# Sheet1.net
KiCad netlist of a schematic drawn in Altium Designer
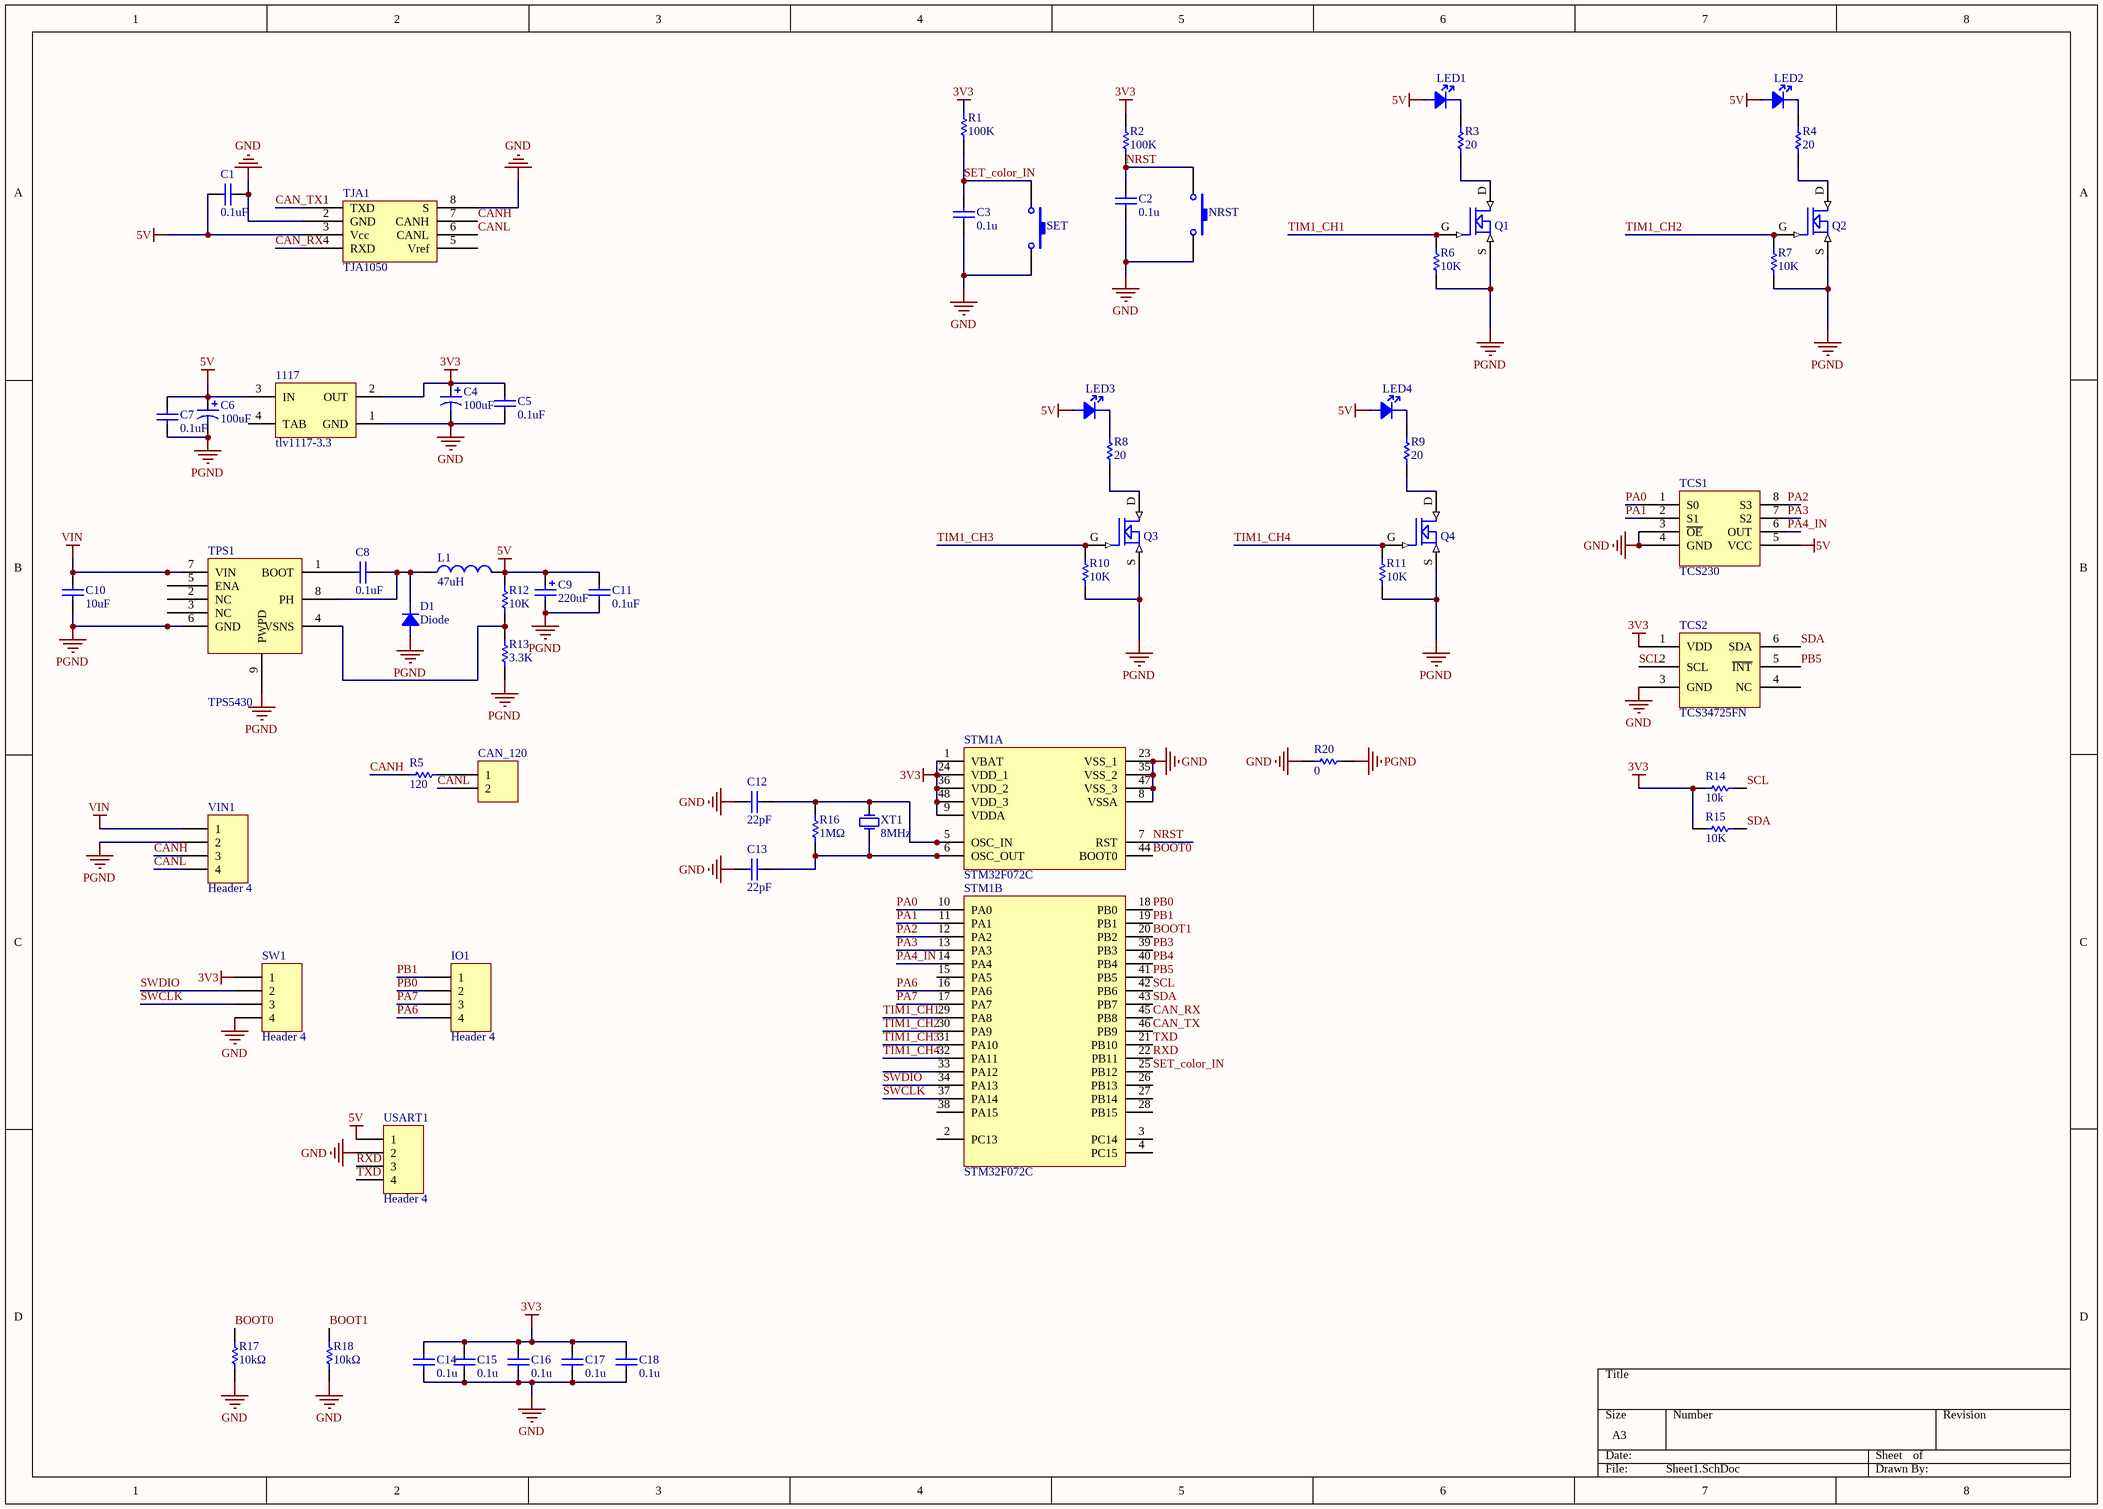
[diagram p0: Sheet1.SchDoc]

(export (version "E")
  (design (tool "Eeschema 10.0.6"))
  (components
    (comp (ref "1117")
      (value "tlv1117-3.3")
      (footprint "LM1117")
      (description "800mA Low-Dropout Linear Regulator")
      (fields
        (field (name "PARTNUMBER") "LM1117IMP-5.0")
        (field (name "MANUFACTURER") "National Semiconductor")
        (field (name "PUBLISHER") "Altium Limited")
      )
      (libsource (lib "K60-mainboard-v3.1") (part "LM1117IMP-5.0"))
    )
    (comp (ref "C1")
      (value "0.1uF")
      (footprint "CAP-MLCC-0603")
      (description "Capacitor")
      (fields (field (name "Comment") "Cap") (field (name "PUBLISHER") "Altium Limited"))
      (libsource (lib "K60-mainboard-v3.1") (part "Cap"))
    )
    (comp (ref "C2")
      (value "0.1u")
      (footprint "CAP-MLCC-0603")
      (description "无极性电容")
      (fields (field (name "PUBLISHER") "Altium Limited"))
      (libsource (lib "Libraries_2014_0618") (part "CAP"))
    )
    (comp (ref "C3")
      (value "0.1u")
      (footprint "CAP-MLCC-0603")
      (description "无极性电容")
      (fields (field (name "PUBLISHER") "Altium Limited"))
      (libsource (lib "Libraries_2014_0618") (part "CAP"))
    )
    (comp (ref "C4")
      (value "100uF")
      (footprint "6032C")
      (description "Polarized Capacitor (Surface Mount)")
      (fields (field (name "Comment") "Cap Pol3") (field (name "PUBLISHER") "Altium Limited"))
      (libsource (lib "K60-mainboard-v3.1") (part "Cap Pol3"))
    )
    (comp (ref "C5")
      (value "0.1uF")
      (footprint "CAP-MLCC-0603")
      (description "Capacitor")
      (fields (field (name "Comment") "Cap") (field (name "PUBLISHER") "Altium Limited"))
      (libsource (lib "K60-mainboard-v3.1") (part "Cap"))
    )
    (comp (ref "C6")
      (value "100uF")
      (footprint "6032C")
      (description "Polarized Capacitor (Surface Mount)")
      (fields (field (name "Comment") "Cap Pol3") (field (name "PUBLISHER") "Altium Limited"))
      (libsource (lib "K60-mainboard-v3.1") (part "Cap Pol3"))
    )
    (comp (ref "C7")
      (value "0.1uF")
      (footprint "CAP-MLCC-0603")
      (description "Capacitor")
      (fields (field (name "Comment") "Cap") (field (name "PUBLISHER") "Altium Limited"))
      (libsource (lib "K60-mainboard-v3.1") (part "Cap"))
    )
    (comp (ref "C8")
      (value "0.1uF")
      (footprint "CAP-MLCC-0603")
      (description "Capacitor")
      (fields (field (name "Comment") "Cap") (field (name "PUBLISHER") "Altium Limited"))
      (libsource (lib "K60-mainboard-v3.1") (part "Cap"))
    )
    (comp (ref "C9")
      (value "220uF")
      (footprint "6032C")
      (description "Polarized Capacitor (Radial)")
      (fields (field (name "Comment") "Cap Pol1") (field (name "PUBLISHER") "Altium Limited"))
      (libsource (lib "K60-mainboard-v3.1") (part "Cap Pol1"))
    )
    (comp (ref "C10")
      (value "10uF")
      (footprint "0805C")
      (description "Capacitor")
      (fields (field (name "Comment") "Cap") (field (name "PUBLISHER") "Altium Limited"))
      (libsource (lib "K60-mainboard-v3.1") (part "Cap"))
    )
    (comp (ref "C11")
      (value "0.1uF")
      (footprint "CAP-MLCC-0603")
      (description "Capacitor")
      (fields (field (name "Comment") "Cap") (field (name "PUBLISHER") "Altium Limited"))
      (libsource (lib "K60-mainboard-v3.1") (part "Cap"))
    )
    (comp (ref "C12")
      (value "22pF")
      (footprint "CAP-MLCC-0603")
      (description "无极性电容")
      (fields (field (name "PUBLISHER") "Altium Limited"))
      (libsource (lib "Libraries_2014_0618") (part "CAP"))
    )
    (comp (ref "C13")
      (value "22pF")
      (footprint "CAP-MLCC-0603")
      (description "无极性电容")
      (fields (field (name "PUBLISHER") "Altium Limited"))
      (libsource (lib "Libraries_2014_0618") (part "CAP"))
    )
    (comp (ref "C14")
      (value "0.1u")
      (footprint "CAP-MLCC-0603")
      (description "无极性电容")
      (fields (field (name "PUBLISHER") "Altium Limited"))
      (libsource (lib "Libraries_2014_0618") (part "CAP"))
    )
    (comp (ref "C15")
      (value "0.1u")
      (footprint "CAP-MLCC-0603")
      (description "无极性电容")
      (fields (field (name "PUBLISHER") "Altium Limited"))
      (libsource (lib "Libraries_2014_0618") (part "CAP"))
    )
    (comp (ref "C16")
      (value "0.1u")
      (footprint "CAP-MLCC-0603")
      (description "无极性电容")
      (fields (field (name "PUBLISHER") "Altium Limited"))
      (libsource (lib "Libraries_2014_0618") (part "CAP"))
    )
    (comp (ref "C17")
      (value "0.1u")
      (footprint "CAP-MLCC-0603")
      (description "无极性电容")
      (fields (field (name "PUBLISHER") "Altium Limited"))
      (libsource (lib "Libraries_2014_0618") (part "CAP"))
    )
    (comp (ref "C18")
      (value "0.1u")
      (footprint "CAP-MLCC-0603")
      (description "无极性电容")
      (fields (field (name "PUBLISHER") "Altium Limited"))
      (libsource (lib "Libraries_2014_0618") (part "CAP"))
    )
    (comp (ref "CAN_120")
      (value "Header 2")
      (footprint "SIP2")
      (description "Header, 2-Pin")
      (fields (field (name "PUBLISHER") "Altium Limited"))
      (libsource (lib "Libraries_2014_0618") (part "Header 2"))
    )
    (comp (ref "D1") (value "Diode") (footprint "SS34") (libsource (lib "K60-mainboard-v3.1") (part "Diode")))
    (comp (ref "IO1")
      (value "Header 4")
      (footprint "HDR1X4")
      (description "Header, 4-Pin")
      (fields (field (name "PUBLISHER") "Altium Limited"))
      (libsource (lib "K60-mainboard-v3.1") (part "Header 4"))
    )
    (comp (ref "L1")
      (value "47uH")
      (footprint "IND_CD52")
      (description "Inductor")
      (fields (field (name "PUBLISHER") "Altium Limited"))
      (libsource (lib "smartcar_example") (part "Inductor"))
    )
    (comp (ref "LED1")
      (value "lED")
      (footprint "LED直插8MM")
      (description "LED")
      (libsource (lib "K60-mainboard-v3.1") (part "00-D-LED"))
    )
    (comp (ref "LED2")
      (value "lED")
      (footprint "LED直插8MM")
      (description "LED")
      (libsource (lib "K60-mainboard-v3.1") (part "00-D-LED"))
    )
    (comp (ref "LED3")
      (value "lED")
      (footprint "LED直插8MM")
      (description "LED")
      (libsource (lib "K60-mainboard-v3.1") (part "00-D-LED"))
    )
    (comp (ref "LED4")
      (value "lED")
      (footprint "LED直插8MM")
      (description "LED")
      (libsource (lib "K60-mainboard-v3.1") (part "00-D-LED"))
    )
    (comp (ref "NRST")
      (value "SW-PB")
      (footprint "KEY")
      (description "Switch")
      (fields (field (name "PUBLISHER") "Altium Limited"))
      (libsource (lib "附加元件") (part "SW-PB"))
    )
    (comp (ref "Q1")
      (value "MOSFET N")
      (footprint "NMOS_SOT23")
      (libsource (lib "K60-mainboard-v3.1") (part "MOSFET N"))
    )
    (comp (ref "Q2")
      (value "MOSFET N")
      (footprint "NMOS_SOT23")
      (libsource (lib "K60-mainboard-v3.1") (part "MOSFET N"))
    )
    (comp (ref "Q3")
      (value "MOSFET N")
      (footprint "NMOS_SOT23")
      (libsource (lib "K60-mainboard-v3.1") (part "MOSFET N"))
    )
    (comp (ref "Q4")
      (value "MOSFET N")
      (footprint "NMOS_SOT23")
      (libsource (lib "K60-mainboard-v3.1") (part "MOSFET N"))
    )
    (comp (ref "R1")
      (value "100K")
      (footprint "RES-0603")
      (description "电阻")
      (fields (field (name "Comment") "RES") (field (name "PUBLISHER") "Altium Limited"))
      (libsource (lib "Libraries_2014_0215") (part "RES"))
    )
    (comp (ref "R2")
      (value "100K")
      (footprint "RES-0603")
      (description "电阻")
      (fields (field (name "Comment") "RES") (field (name "PUBLISHER") "Altium Limited"))
      (libsource (lib "Libraries_2014_0215") (part "RES"))
    )
    (comp (ref "R3")
      (value "20")
      (footprint "RES-0805")
      (description "电阻")
      (fields (field (name "PUBLISHER") "Altium Limited"))
      (libsource (lib "Libraries_2014_0618") (part "RES"))
    )
    (comp (ref "R4")
      (value "20")
      (footprint "RES-0805")
      (description "电阻")
      (fields (field (name "PUBLISHER") "Altium Limited"))
      (libsource (lib "Libraries_2014_0618") (part "RES"))
    )
    (comp (ref "R5")
      (value "120")
      (footprint "RES-0603")
      (description "Resistor")
      (fields (field (name "Comment") "Res1") (field (name "PUBLISHER") "Altium Limited"))
      (libsource (lib "K60-mainboard-v3.1") (part "Res1"))
    )
    (comp (ref "R6")
      (value "10K")
      (footprint "RES-0603")
      (description "电阻")
      (fields (field (name "PUBLISHER") "Altium Limited"))
      (libsource (lib "Libraries_2014_0618") (part "RES"))
    )
    (comp (ref "R7")
      (value "10K")
      (footprint "RES-0603")
      (description "电阻")
      (fields (field (name "PUBLISHER") "Altium Limited"))
      (libsource (lib "Libraries_2014_0618") (part "RES"))
    )
    (comp (ref "R8")
      (value "20")
      (footprint "RES-0805")
      (description "电阻")
      (fields (field (name "PUBLISHER") "Altium Limited"))
      (libsource (lib "Libraries_2014_0618") (part "RES"))
    )
    (comp (ref "R9")
      (value "20")
      (footprint "RES-0805")
      (description "电阻")
      (fields (field (name "PUBLISHER") "Altium Limited"))
      (libsource (lib "Libraries_2014_0618") (part "RES"))
    )
    (comp (ref "R10")
      (value "10K")
      (footprint "RES-0603")
      (description "电阻")
      (fields (field (name "PUBLISHER") "Altium Limited"))
      (libsource (lib "Libraries_2014_0618") (part "RES"))
    )
    (comp (ref "R11")
      (value "10K")
      (footprint "RES-0603")
      (description "电阻")
      (fields (field (name "PUBLISHER") "Altium Limited"))
      (libsource (lib "Libraries_2014_0618") (part "RES"))
    )
    (comp (ref "R12")
      (value "10K")
      (footprint "RES-0603")
      (description "Resistor")
      (fields (field (name "Comment") "Res1") (field (name "PUBLISHER") "Altium Limited"))
      (libsource (lib "K60-mainboard-v3.1") (part "Res1"))
    )
    (comp (ref "R13")
      (value "3.3K")
      (footprint "RES-0603")
      (description "Resistor")
      (fields (field (name "Comment") "Res1") (field (name "PUBLISHER") "Altium Limited"))
      (libsource (lib "K60-mainboard-v3.1") (part "Res1"))
    )
    (comp (ref "R14")
      (value "10k")
      (footprint "RES-0603")
      (description "电阻")
      (fields (field (name "PUBLISHER") "Altium Limited"))
      (libsource (lib "Libraries_2014_0618") (part "RES"))
    )
    (comp (ref "R15")
      (value "10K")
      (footprint "RES-0603")
      (description "电阻")
      (fields (field (name "PUBLISHER") "Altium Limited"))
      (libsource (lib "Libraries_2014_0618") (part "RES"))
    )
    (comp (ref "R16")
      (value "1MΩ")
      (footprint "RES-0603")
      (description "电阻")
      (fields (field (name "PUBLISHER") "Altium Limited"))
      (libsource (lib "Libraries_2014_0618") (part "RES"))
    )
    (comp (ref "R17")
      (value "10kΩ")
      (footprint "RES-0603")
      (description "电阻")
      (fields (field (name "Comment") "RES") (field (name "PUBLISHER") "Altium Limited"))
      (libsource (lib "Libraries_2014_0215") (part "RES"))
    )
    (comp (ref "R18")
      (value "10kΩ")
      (footprint "RES-0603")
      (description "电阻")
      (fields (field (name "Comment") "RES") (field (name "PUBLISHER") "Altium Limited"))
      (libsource (lib "Libraries_2014_0215") (part "RES"))
    )
    (comp (ref "R20")
      (value "0")
      (footprint "RES-0805")
      (description "电阻")
      (fields (field (name "PUBLISHER") "Altium Limited"))
      (libsource (lib "Libraries_2014_0618") (part "RES"))
    )
    (comp (ref "SET")
      (value "SW-PB")
      (footprint "KEY")
      (description "Switch")
      (fields (field (name "PUBLISHER") "Altium Limited"))
      (libsource (lib "附加元件") (part "SW-PB"))
    )
    (comp (ref "STM1")
      (value "STM32F072C")
      (footprint "PCB_IntegratedCircuit:LQFP_P0.5_48")
      (description "MCU")
      (libsource (lib "SCH_IntegratedCircuit") (part "STM32F103C"))
    )
    (comp (ref "SW1")
      (value "Header 4")
      (footprint "HDR1X4")
      (description "Header, 4-Pin")
      (fields (field (name "PUBLISHER") "Altium Limited"))
      (libsource (lib "K60-mainboard-v3.1") (part "Header 4"))
    )
    (comp (ref "TCS1")
      (value "TCS230")
      (footprint "SOP_E150_8")
      (libsource (lib "SCH_IntegratedCircuit") (part "TCS230"))
    )
    (comp (ref "TCS2")
      (value "TCS34725FN")
      (footprint "DFN-6")
      (description "颜色传感器")
      (libsource (lib "SCH_IntegratedCircuit") (part "TCS34725FN"))
    )
    (comp (ref "TJA1")
      (value "TJA1050")
      (footprint "TJA1050")
      (description "CAN总线收发器")
      (libsource (lib "Libraries_2014_0618") (part "TJA1050"))
    )
    (comp (ref "TPS1")
      (value "TPS5430")
      (footprint "TPS5430")
      (libsource (lib "K60-mainboard-v3.1") (part "TPS5430"))
    )
    (comp (ref "USART1")
      (value "Header 4")
      (footprint "HDR1X4")
      (description "Header, 4-Pin")
      (fields (field (name "PUBLISHER") "Altium Limited"))
      (libsource (lib "K60-mainboard-v3.1") (part "Header 4"))
    )
    (comp (ref "VIN1")
      (value "Header 4")
      (footprint "connector:XH-2.54pin4")
      (description "Header, 4-Pin")
      (fields (field (name "PUBLISHER") "Altium Limited"))
      (libsource (lib "K60-mainboard-v3.1") (part "Header 4"))
    )
    (comp (ref "XT1")
      (value "8MHz")
      (footprint "PCB_Oscillator:XT_5032_2")
      (description "Crystal Oscillator")
      (fields (field (name "Comment") "XTAL_5032_2P"))
      (libsource (lib "SCH_Oscillator") (part "XTAL_5032_2P"))
    )
  )
  (nets
    (net (code "1") (name "/BOOT0") (class "Default")
      (node (ref "R17") (pin "2") (pinfunction "2_2") (pintype "passive"))
      (node (ref "STM1") (pin "44") (pinfunction "BOOT0_44") (pintype "passive"))
    )
    (net (code "2") (name "/BOOT1") (class "Default")
      (node (ref "R18") (pin "2") (pinfunction "2_2") (pintype "passive"))
      (node (ref "STM1") (pin "20") (pinfunction "PB2_20") (pintype "passive"))
    )
    (net (code "3") (name "/CANH") (class "Default")
      (node (ref "R5") (pin "2") (pinfunction "2_2") (pintype "passive"))
      (node (ref "TJA1") (pin "7") (pinfunction "CANH_7") (pintype "passive"))
      (node (ref "VIN1") (pin "3") (pinfunction "3_3") (pintype "passive"))
    )
    (net (code "4") (name "/CANL") (class "Default")
      (node (ref "CAN_120") (pin "2") (pinfunction "2_2") (pintype "passive"))
      (node (ref "TJA1") (pin "6") (pinfunction "CANL_6") (pintype "passive"))
      (node (ref "VIN1") (pin "4") (pinfunction "4_4") (pintype "passive"))
    )
    (net (code "5") (name "/CAN_RX") (class "Default")
      (node (ref "STM1") (pin "45") (pinfunction "PB8_45") (pintype "passive"))
      (node (ref "TJA1") (pin "4") (pinfunction "RXD_4") (pintype "passive"))
    )
    (net (code "6") (name "/CAN_TX") (class "Default")
      (node (ref "STM1") (pin "46") (pinfunction "PB9_46") (pintype "passive"))
      (node (ref "TJA1") (pin "1") (pinfunction "TXD_1") (pintype "passive"))
    )
    (net (code "7") (name "/NRST") (class "Default")
      (node (ref "C2") (pin "2") (pinfunction "2_2") (pintype "passive"))
      (node (ref "NRST") (pin "1") (pinfunction "1_1") (pintype "passive"))
      (node (ref "R2") (pin "1") (pinfunction "1_1") (pintype "passive"))
      (node (ref "STM1") (pin "7") (pinfunction "RST_7") (pintype "passive"))
    )
    (net (code "8") (name "/PA0") (class "Default")
      (node (ref "STM1") (pin "10") (pinfunction "PA0_10") (pintype "passive"))
      (node (ref "TCS1") (pin "1") (pinfunction "S0_1") (pintype "passive"))
    )
    (net (code "9") (name "/PA1") (class "Default")
      (node (ref "STM1") (pin "11") (pinfunction "PA1_11") (pintype "passive"))
      (node (ref "TCS1") (pin "2") (pinfunction "S1_2") (pintype "passive"))
    )
    (net (code "10") (name "/PA2") (class "Default")
      (node (ref "STM1") (pin "12") (pinfunction "PA2_12") (pintype "passive"))
      (node (ref "TCS1") (pin "8") (pinfunction "S3_8") (pintype "passive"))
    )
    (net (code "11") (name "/PA3") (class "Default")
      (node (ref "STM1") (pin "13") (pinfunction "PA3_13") (pintype "passive"))
      (node (ref "TCS1") (pin "7") (pinfunction "S2_7") (pintype "passive"))
    )
    (net (code "12") (name "/PA4_IN") (class "Default")
      (node (ref "STM1") (pin "14") (pinfunction "PA4_14") (pintype "passive"))
      (node (ref "TCS1") (pin "6") (pinfunction "OUT_6") (pintype "passive"))
    )
    (net (code "13") (name "/PA6") (class "Default")
      (node (ref "IO1") (pin "4") (pinfunction "4_4") (pintype "passive"))
      (node (ref "STM1") (pin "16") (pinfunction "PA6_16") (pintype "passive"))
    )
    (net (code "14") (name "/PA7") (class "Default")
      (node (ref "IO1") (pin "3") (pinfunction "3_3") (pintype "passive"))
      (node (ref "STM1") (pin "17") (pinfunction "PA7_17") (pintype "passive"))
    )
    (net (code "15") (name "/PB0") (class "Default")
      (node (ref "IO1") (pin "2") (pinfunction "2_2") (pintype "passive"))
      (node (ref "STM1") (pin "18") (pinfunction "PB0_18") (pintype "passive"))
    )
    (net (code "16") (name "/PB1") (class "Default")
      (node (ref "IO1") (pin "1") (pinfunction "1_1") (pintype "passive"))
      (node (ref "STM1") (pin "19") (pinfunction "PB1_19") (pintype "passive"))
    )
    (net (code "17") (name "/PB3") (class "Default")
      (node (ref "STM1") (pin "39") (pinfunction "PB3_39") (pintype "passive"))
    )
    (net (code "18") (name "/PB4") (class "Default")
      (node (ref "STM1") (pin "40") (pinfunction "PB4_40") (pintype "passive"))
    )
    (net (code "19") (name "/PB5") (class "Default")
      (node (ref "STM1") (pin "41") (pinfunction "PB5_41") (pintype "passive"))
      (node (ref "TCS2") (pin "5") (pinfunction "~{INT}_5") (pintype "passive"))
    )
    (net (code "20") (name "/RXD") (class "Default")
      (node (ref "STM1") (pin "22") (pinfunction "PB11_22") (pintype "passive"))
      (node (ref "USART1") (pin "3") (pinfunction "3_3") (pintype "passive"))
    )
    (net (code "21") (name "/SCL") (class "Default")
      (node (ref "R14") (pin "2") (pinfunction "2_2") (pintype "passive"))
      (node (ref "STM1") (pin "42") (pinfunction "PB6_42") (pintype "passive"))
      (node (ref "TCS2") (pin "2") (pinfunction "SCL_2") (pintype "passive"))
    )
    (net (code "22") (name "/SDA") (class "Default")
      (node (ref "R15") (pin "2") (pinfunction "2_2") (pintype "passive"))
      (node (ref "STM1") (pin "43") (pinfunction "PB7_43") (pintype "passive"))
      (node (ref "TCS2") (pin "6") (pinfunction "SDA_6") (pintype "passive"))
    )
    (net (code "23") (name "/SET_color_IN") (class "Default")
      (node (ref "C3") (pin "2") (pinfunction "2_2") (pintype "passive"))
      (node (ref "R1") (pin "1") (pinfunction "1_1") (pintype "passive"))
      (node (ref "SET") (pin "1") (pinfunction "1_1") (pintype "passive"))
      (node (ref "STM1") (pin "25") (pinfunction "PB12_25") (pintype "passive"))
    )
    (net (code "24") (name "/SWCLK") (class "Default")
      (node (ref "STM1") (pin "37") (pinfunction "PA14_37") (pintype "passive"))
      (node (ref "SW1") (pin "3") (pinfunction "3_3") (pintype "passive"))
    )
    (net (code "25") (name "/SWDIO") (class "Default")
      (node (ref "STM1") (pin "34") (pinfunction "PA13_34") (pintype "passive"))
      (node (ref "SW1") (pin "2") (pinfunction "2_2") (pintype "passive"))
    )
    (net (code "26") (name "/TIM1_CH1") (class "Default")
      (node (ref "Q1") (pin "G") (pinfunction "G_G") (pintype "input"))
      (node (ref "R6") (pin "1") (pinfunction "1_1") (pintype "passive"))
      (node (ref "STM1") (pin "29") (pinfunction "PA8_29") (pintype "passive"))
    )
    (net (code "27") (name "/TIM1_CH2") (class "Default")
      (node (ref "Q2") (pin "G") (pinfunction "G_G") (pintype "input"))
      (node (ref "R7") (pin "1") (pinfunction "1_1") (pintype "passive"))
      (node (ref "STM1") (pin "30") (pinfunction "PA9_30") (pintype "passive"))
    )
    (net (code "28") (name "/TIM1_CH3") (class "Default")
      (node (ref "Q3") (pin "G") (pinfunction "G_G") (pintype "input"))
      (node (ref "R10") (pin "1") (pinfunction "1_1") (pintype "passive"))
      (node (ref "STM1") (pin "31") (pinfunction "PA10_31") (pintype "passive"))
    )
    (net (code "29") (name "/TIM1_CH4") (class "Default")
      (node (ref "Q4") (pin "G") (pinfunction "G_G") (pintype "input"))
      (node (ref "R11") (pin "1") (pinfunction "1_1") (pintype "passive"))
      (node (ref "STM1") (pin "32") (pinfunction "PA11_32") (pintype "passive"))
    )
    (net (code "30") (name "/TXD") (class "Default")
      (node (ref "STM1") (pin "21") (pinfunction "PB10_21") (pintype "passive"))
      (node (ref "USART1") (pin "4") (pinfunction "4_4") (pintype "passive"))
    )
    (net (code "31") (name "3V3") (class "Default")
      (node (ref "1117") (pin "2") (pinfunction "OUT_2") (pintype "power_in"))
      (node (ref "C14") (pin "2") (pinfunction "2_2") (pintype "passive"))
      (node (ref "C15") (pin "2") (pinfunction "2_2") (pintype "passive"))
      (node (ref "C16") (pin "2") (pinfunction "2_2") (pintype "passive"))
      (node (ref "C17") (pin "2") (pinfunction "2_2") (pintype "passive"))
      (node (ref "C18") (pin "2") (pinfunction "2_2") (pintype "passive"))
      (node (ref "C4") (pin "1") (pinfunction "1_1") (pintype "passive"))
      (node (ref "C5") (pin "1") (pinfunction "1_1") (pintype "passive"))
      (node (ref "R1") (pin "2") (pinfunction "2_2") (pintype "passive"))
      (node (ref "R14") (pin "1") (pinfunction "1_1") (pintype "passive"))
      (node (ref "R15") (pin "1") (pinfunction "1_1") (pintype "passive"))
      (node (ref "R2") (pin "2") (pinfunction "2_2") (pintype "passive"))
      (node (ref "STM1") (pin "1") (pinfunction "VBAT_1") (pintype "passive"))
      (node (ref "STM1") (pin "24") (pinfunction "VDD_1_24") (pintype "passive"))
      (node (ref "STM1") (pin "36") (pinfunction "VDD_2_36") (pintype "passive"))
      (node (ref "STM1") (pin "48") (pinfunction "VDD_3_48") (pintype "passive"))
      (node (ref "STM1") (pin "9") (pinfunction "VDDA_9") (pintype "passive"))
      (node (ref "SW1") (pin "1") (pinfunction "1_1") (pintype "passive"))
      (node (ref "TCS2") (pin "1") (pinfunction "VDD_1") (pintype "passive"))
    )
    (net (code "32") (name "5V") (class "Default")
      (node (ref "1117") (pin "3") (pinfunction "IN_3") (pintype "power_in"))
      (node (ref "C1") (pin "1") (pinfunction "1_1") (pintype "passive"))
      (node (ref "C11") (pin "2") (pinfunction "2_2") (pintype "passive"))
      (node (ref "C6") (pin "1") (pinfunction "1_1") (pintype "passive"))
      (node (ref "C7") (pin "1") (pinfunction "1_1") (pintype "passive"))
      (node (ref "C9") (pin "1") (pinfunction "1_1") (pintype "passive"))
      (node (ref "L1") (pin "2") (pinfunction "2_2") (pintype "passive"))
      (node (ref "LED1") (pin "A") (pinfunction "1_A") (pintype "passive"))
      (node (ref "LED2") (pin "A") (pinfunction "1_A") (pintype "passive"))
      (node (ref "LED3") (pin "A") (pinfunction "1_A") (pintype "passive"))
      (node (ref "LED4") (pin "A") (pinfunction "1_A") (pintype "passive"))
      (node (ref "R12") (pin "2") (pinfunction "2_2") (pintype "passive"))
      (node (ref "TCS1") (pin "5") (pinfunction "VCC_5") (pintype "passive"))
      (node (ref "TJA1") (pin "3") (pinfunction "Vcc_3") (pintype "passive"))
      (node (ref "USART1") (pin "1") (pinfunction "1_1") (pintype "passive"))
    )
    (net (code "33") (name "GND") (class "Default")
      (node (ref "1117") (pin "1") (pinfunction "GND_1") (pintype "power_in"))
      (node (ref "C1") (pin "2") (pinfunction "2_2") (pintype "passive"))
      (node (ref "C12") (pin "1") (pinfunction "1_1") (pintype "passive"))
      (node (ref "C13") (pin "1") (pinfunction "1_1") (pintype "passive"))
      (node (ref "C14") (pin "1") (pinfunction "1_1") (pintype "passive"))
      (node (ref "C15") (pin "1") (pinfunction "1_1") (pintype "passive"))
      (node (ref "C16") (pin "1") (pinfunction "1_1") (pintype "passive"))
      (node (ref "C17") (pin "1") (pinfunction "1_1") (pintype "passive"))
      (node (ref "C18") (pin "1") (pinfunction "1_1") (pintype "passive"))
      (node (ref "C2") (pin "1") (pinfunction "1_1") (pintype "passive"))
      (node (ref "C3") (pin "1") (pinfunction "1_1") (pintype "passive"))
      (node (ref "C4") (pin "2") (pinfunction "2_2") (pintype "passive"))
      (node (ref "C5") (pin "2") (pinfunction "2_2") (pintype "passive"))
      (node (ref "NRST") (pin "2") (pinfunction "2_2") (pintype "passive"))
      (node (ref "R17") (pin "1") (pinfunction "1_1") (pintype "passive"))
      (node (ref "R18") (pin "1") (pinfunction "1_1") (pintype "passive"))
      (node (ref "R20") (pin "1") (pinfunction "1_1") (pintype "passive"))
      (node (ref "SET") (pin "2") (pinfunction "2_2") (pintype "passive"))
      (node (ref "STM1") (pin "23") (pinfunction "VSS_1_23") (pintype "passive"))
      (node (ref "STM1") (pin "35") (pinfunction "VSS_2_35") (pintype "passive"))
      (node (ref "STM1") (pin "47") (pinfunction "VSS_3_47") (pintype "passive"))
      (node (ref "STM1") (pin "8") (pinfunction "VSSA_8") (pintype "passive"))
      (node (ref "SW1") (pin "4") (pinfunction "4_4") (pintype "passive"))
      (node (ref "TCS1") (pin "3") (pinfunction "~{OE}_3") (pintype "passive"))
      (node (ref "TCS1") (pin "4") (pinfunction "GND_4") (pintype "passive"))
      (node (ref "TCS2") (pin "3") (pinfunction "GND_3") (pintype "passive"))
      (node (ref "TJA1") (pin "2") (pinfunction "GND_2") (pintype "passive"))
      (node (ref "TJA1") (pin "8") (pinfunction "S_8") (pintype "passive"))
      (node (ref "USART1") (pin "2") (pinfunction "2_2") (pintype "passive"))
    )
    (net (code "34") (name "Net-(CAN_120-Pad1)") (class "Default")
      (node (ref "CAN_120") (pin "1") (pinfunction "1_1") (pintype "passive"))
      (node (ref "R5") (pin "1") (pinfunction "1_1") (pintype "passive"))
    )
    (net (code "35") (name "Net-(D1-2)") (class "Default")
      (node (ref "C8") (pin "2") (pinfunction "2_2") (pintype "passive"))
      (node (ref "D1") (pin "K") (pinfunction "2_K") (pintype "passive"))
      (node (ref "L1") (pin "1") (pinfunction "1_1") (pintype "passive"))
      (node (ref "TPS1") (pin "8") (pinfunction "PH_8") (pintype "passive"))
    )
    (net (code "36") (name "Net-(LED1-2)") (class "Default")
      (node (ref "LED1") (pin "K") (pinfunction "2_K") (pintype "passive"))
      (node (ref "R3") (pin "1") (pinfunction "1_1") (pintype "passive"))
    )
    (net (code "37") (name "Net-(LED2-2)") (class "Default")
      (node (ref "LED2") (pin "K") (pinfunction "2_K") (pintype "passive"))
      (node (ref "R4") (pin "1") (pinfunction "1_1") (pintype "passive"))
    )
    (net (code "38") (name "Net-(LED3-2)") (class "Default")
      (node (ref "LED3") (pin "K") (pinfunction "2_K") (pintype "passive"))
      (node (ref "R8") (pin "1") (pinfunction "1_1") (pintype "passive"))
    )
    (net (code "39") (name "Net-(LED4-2)") (class "Default")
      (node (ref "LED4") (pin "K") (pinfunction "2_K") (pintype "passive"))
      (node (ref "R9") (pin "1") (pinfunction "1_1") (pintype "passive"))
    )
    (net (code "40") (name "Net-(Q1-PadD)") (class "Default")
      (node (ref "Q1") (pin "D") (pinfunction "D_D") (pintype "input"))
      (node (ref "R3") (pin "2") (pinfunction "2_2") (pintype "passive"))
    )
    (net (code "41") (name "Net-(Q2-PadD)") (class "Default")
      (node (ref "Q2") (pin "D") (pinfunction "D_D") (pintype "input"))
      (node (ref "R4") (pin "2") (pinfunction "2_2") (pintype "passive"))
    )
    (net (code "42") (name "Net-(Q3-PadD)") (class "Default")
      (node (ref "Q3") (pin "D") (pinfunction "D_D") (pintype "input"))
      (node (ref "R8") (pin "2") (pinfunction "2_2") (pintype "passive"))
    )
    (net (code "43") (name "Net-(Q4-PadD)") (class "Default")
      (node (ref "Q4") (pin "D") (pinfunction "D_D") (pintype "input"))
      (node (ref "R9") (pin "2") (pinfunction "2_2") (pintype "passive"))
    )
    (net (code "44") (name "Net-(STM1A-OSC_IN)") (class "Default")
      (node (ref "C12") (pin "2") (pinfunction "2_2") (pintype "passive"))
      (node (ref "R16") (pin "2") (pinfunction "2_2") (pintype "passive"))
      (node (ref "STM1") (pin "5") (pinfunction "OSC_IN_5") (pintype "passive"))
      (node (ref "XT1") (pin "2") (pinfunction "OSC2_2") (pintype "passive"))
    )
    (net (code "45") (name "Net-(STM1A-OSC_OUT)") (class "Default")
      (node (ref "C13") (pin "2") (pinfunction "2_2") (pintype "passive"))
      (node (ref "R16") (pin "1") (pinfunction "1_1") (pintype "passive"))
      (node (ref "STM1") (pin "6") (pinfunction "OSC_OUT_6") (pintype "passive"))
      (node (ref "XT1") (pin "1") (pinfunction "OSC1_1") (pintype "passive"))
    )
    (net (code "46") (name "Net-(TPS1-BOOT)") (class "Default")
      (node (ref "C8") (pin "1") (pinfunction "1_1") (pintype "passive"))
      (node (ref "TPS1") (pin "1") (pinfunction "BOOT_1") (pintype "passive"))
    )
    (net (code "47") (name "Net-(TPS1-VSNS)") (class "Default")
      (node (ref "R12") (pin "1") (pinfunction "1_1") (pintype "passive"))
      (node (ref "R13") (pin "2") (pinfunction "2_2") (pintype "passive"))
      (node (ref "TPS1") (pin "4") (pinfunction "VSNS_4") (pintype "passive"))
    )
    (net (code "48") (name "PGND") (class "Default")
      (node (ref "C10") (pin "1") (pinfunction "1_1") (pintype "passive"))
      (node (ref "C11") (pin "1") (pinfunction "1_1") (pintype "passive"))
      (node (ref "C6") (pin "2") (pinfunction "2_2") (pintype "passive"))
      (node (ref "C7") (pin "2") (pinfunction "2_2") (pintype "passive"))
      (node (ref "C9") (pin "2") (pinfunction "2_2") (pintype "passive"))
      (node (ref "D1") (pin "A") (pinfunction "1_A") (pintype "passive"))
      (node (ref "Q1") (pin "S") (pinfunction "S_S") (pintype "input"))
      (node (ref "Q2") (pin "S") (pinfunction "S_S") (pintype "input"))
      (node (ref "Q3") (pin "S") (pinfunction "S_S") (pintype "input"))
      (node (ref "Q4") (pin "S") (pinfunction "S_S") (pintype "input"))
      (node (ref "R10") (pin "2") (pinfunction "2_2") (pintype "passive"))
      (node (ref "R11") (pin "2") (pinfunction "2_2") (pintype "passive"))
      (node (ref "R13") (pin "1") (pinfunction "1_1") (pintype "passive"))
      (node (ref "R20") (pin "2") (pinfunction "2_2") (pintype "passive"))
      (node (ref "R6") (pin "2") (pinfunction "2_2") (pintype "passive"))
      (node (ref "R7") (pin "2") (pinfunction "2_2") (pintype "passive"))
      (node (ref "TPS1") (pin "6") (pinfunction "GND_6") (pintype "passive"))
      (node (ref "TPS1") (pin "9") (pinfunction "PWPD_9") (pintype "passive"))
      (node (ref "VIN1") (pin "2") (pinfunction "2_2") (pintype "passive"))
    )
    (net (code "49") (name "VIN") (class "Default")
      (node (ref "C10") (pin "2") (pinfunction "2_2") (pintype "passive"))
      (node (ref "TPS1") (pin "7") (pinfunction "VIN_7") (pintype "passive"))
      (node (ref "VIN1") (pin "1") (pinfunction "1_1") (pintype "passive"))
    )
    (net (code "50") (name "unconnected-(1117-TAB-Pad4)") (class "Default")
      (node (ref "1117") (pin "4") (pinfunction "TAB_4") (pintype "power_in"))
    )
    (net (code "51") (name "unconnected-(STM1B-PA5-Pad15)") (class "Default")
      (node (ref "STM1") (pin "15") (pinfunction "PA5_15") (pintype "passive"))
    )
    (net (code "52") (name "unconnected-(STM1B-PA12-Pad33)") (class "Default")
      (node (ref "STM1") (pin "33") (pinfunction "PA12_33") (pintype "passive"))
    )
    (net (code "53") (name "unconnected-(STM1B-PA15-Pad38)") (class "Default")
      (node (ref "STM1") (pin "38") (pinfunction "PA15_38") (pintype "passive"))
    )
    (net (code "54") (name "unconnected-(STM1B-PB13-Pad26)") (class "Default")
      (node (ref "STM1") (pin "26") (pinfunction "PB13_26") (pintype "passive"))
    )
    (net (code "55") (name "unconnected-(STM1B-PB14-Pad27)") (class "Default")
      (node (ref "STM1") (pin "27") (pinfunction "PB14_27") (pintype "passive"))
    )
    (net (code "56") (name "unconnected-(STM1B-PB15-Pad28)") (class "Default")
      (node (ref "STM1") (pin "28") (pinfunction "PB15_28") (pintype "passive"))
    )
    (net (code "57") (name "unconnected-(STM1B-PC13-Pad2)") (class "Default")
      (node (ref "STM1") (pin "2") (pinfunction "PC13_2") (pintype "passive"))
    )
    (net (code "58") (name "unconnected-(STM1B-PC14-Pad3)") (class "Default")
      (node (ref "STM1") (pin "3") (pinfunction "PC14_3") (pintype "passive"))
    )
    (net (code "59") (name "unconnected-(STM1B-PC15-Pad4)") (class "Default")
      (node (ref "STM1") (pin "4") (pinfunction "PC15_4") (pintype "passive"))
    )
    (net (code "60") (name "unconnected-(TCS2-NC-Pad4)") (class "Default")
      (node (ref "TCS2") (pin "4") (pinfunction "NC_4") (pintype "passive"))
    )
    (net (code "61") (name "unconnected-(TJA1-Vref-Pad5)") (class "Default")
      (node (ref "TJA1") (pin "5") (pinfunction "Vref_5") (pintype "passive"))
    )
    (net (code "62") (name "unconnected-(TPS1-ENA-Pad5)") (class "Default")
      (node (ref "TPS1") (pin "5") (pinfunction "ENA_5") (pintype "passive"))
    )
    (net (code "63") (name "unconnected-(TPS1-NC-Pad2)") (class "Default")
      (node (ref "TPS1") (pin "2") (pinfunction "NC_2") (pintype "passive"))
    )
    (net (code "64") (name "unconnected-(TPS1-NC-Pad3)") (class "Default")
      (node (ref "TPS1") (pin "3") (pinfunction "NC_3") (pintype "passive"))
    )
  )
)
